# dam1941_extender.net
KiCad netlist of a schematic drawn in EAGLE
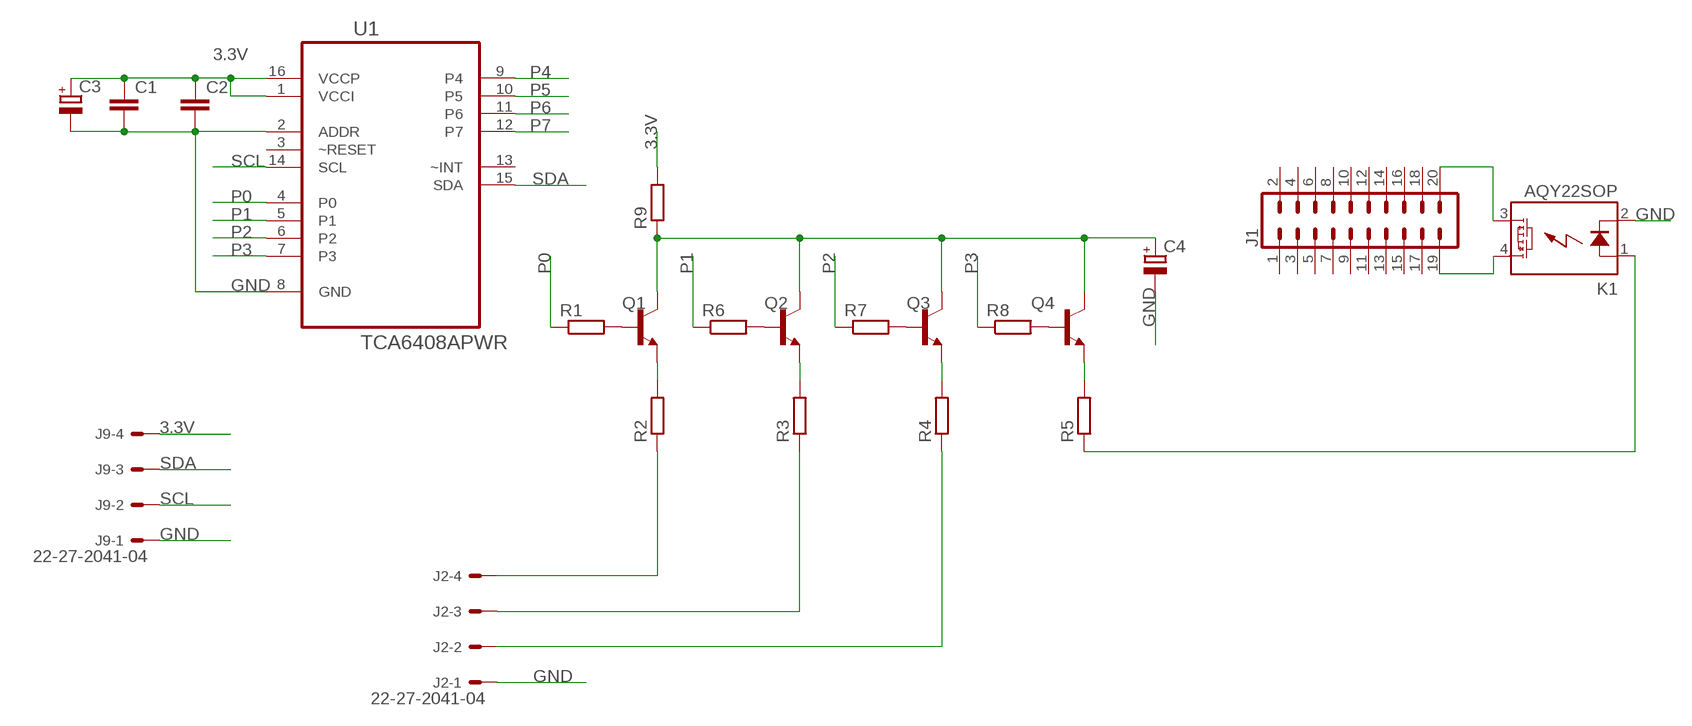
[diagram p0: schematic, sheet 1]

(export (version "E")
  (design (tool "Eeschema 10.0.6"))
  (components
    (comp (ref "C1")
      (value "C-EUC0805")
      (footprint "eagle-import:C0805")
      (libsource (lib "eagle-import") (part "C-EUC0805"))
    )
    (comp (ref "C2")
      (value "C-EUC0805")
      (footprint "eagle-import:C0805")
      (libsource (lib "eagle-import") (part "C-EUC0805"))
    )
    (comp (ref "C3")
      (value "CPOL-EUE2.5-6")
      (footprint "eagle-import:E2,5-6")
      (libsource (lib "eagle-import") (part "CPOL-EUE2.5-6"))
    )
    (comp (ref "C4")
      (value "CPOL-EUE2.5-6")
      (footprint "eagle-import:E2,5-6")
      (libsource (lib "eagle-import") (part "CPOL-EUE2.5-6"))
    )
    (comp (ref "J1")
      (value "CONN_10X22X10_LOCK")
      (footprint "eagle-import:2X10_LOCK")
      (libsource (lib "eagle-import") (part "CONN_10X22X10_LOCK"))
    )
    (comp (ref "J2")
      (value "22-27-2041-04")
      (footprint "eagle-import:6410-04")
      (fields (field (name "MF") "MOLEX"))
      (libsource (lib "eagle-import") (part "22-?-0427-2041"))
    )
    (comp (ref "J9")
      (value "22-27-2041-04")
      (footprint "eagle-import:6410-04")
      (fields (field (name "MF") "MOLEX"))
      (libsource (lib "eagle-import") (part "22-?-0427-2041"))
    )
    (comp (ref "K1")
      (value "AQY22SOP")
      (footprint "eagle-import:SOP04")
      (libsource (lib "eagle-import") (part "AQYSOP22"))
    )
    (comp (ref "Q1")
      (value "TRANSISTOR_BC850-NPN-SOT23-BEC")
      (footprint "eagle-import:TRANSISTOR_SOT23-BEC")
      (libsource (lib "eagle-import") (part "TRANSISTOR_-NPN-SOT23-BECBC850"))
    )
    (comp (ref "Q2")
      (value "TRANSISTOR_BC850-NPN-SOT23-BEC")
      (footprint "eagle-import:TRANSISTOR_SOT23-BEC")
      (libsource (lib "eagle-import") (part "TRANSISTOR_-NPN-SOT23-BECBC850"))
    )
    (comp (ref "Q3")
      (value "TRANSISTOR_BC850-NPN-SOT23-BEC")
      (footprint "eagle-import:TRANSISTOR_SOT23-BEC")
      (libsource (lib "eagle-import") (part "TRANSISTOR_-NPN-SOT23-BECBC850"))
    )
    (comp (ref "Q4")
      (value "TRANSISTOR_BC850-NPN-SOT23-BEC")
      (footprint "eagle-import:TRANSISTOR_SOT23-BEC")
      (libsource (lib "eagle-import") (part "TRANSISTOR_-NPN-SOT23-BECBC850"))
    )
    (comp (ref "R1")
      (value "R-EU_MELF0204W")
      (footprint "eagle-import:MINI_MELF-0204W")
      (libsource (lib "eagle-import") (part "R-EU_MELF0204W"))
    )
    (comp (ref "R2")
      (value "R-EU_MELF0204W")
      (footprint "eagle-import:MINI_MELF-0204W")
      (libsource (lib "eagle-import") (part "R-EU_MELF0204W"))
    )
    (comp (ref "R3")
      (value "R-EU_MELF0204W")
      (footprint "eagle-import:MINI_MELF-0204W")
      (libsource (lib "eagle-import") (part "R-EU_MELF0204W"))
    )
    (comp (ref "R4")
      (value "R-EU_MELF0204W")
      (footprint "eagle-import:MINI_MELF-0204W")
      (libsource (lib "eagle-import") (part "R-EU_MELF0204W"))
    )
    (comp (ref "R5")
      (value "R-EU_MELF0204W")
      (footprint "eagle-import:MINI_MELF-0204W")
      (libsource (lib "eagle-import") (part "R-EU_MELF0204W"))
    )
    (comp (ref "R6")
      (value "R-EU_MELF0204W")
      (footprint "eagle-import:MINI_MELF-0204W")
      (libsource (lib "eagle-import") (part "R-EU_MELF0204W"))
    )
    (comp (ref "R7")
      (value "R-EU_MELF0204W")
      (footprint "eagle-import:MINI_MELF-0204W")
      (libsource (lib "eagle-import") (part "R-EU_MELF0204W"))
    )
    (comp (ref "R8")
      (value "R-EU_MELF0204W")
      (footprint "eagle-import:MINI_MELF-0204W")
      (libsource (lib "eagle-import") (part "R-EU_MELF0204W"))
    )
    (comp (ref "R9")
      (value "R-EU_MELF0204W")
      (footprint "eagle-import:MINI_MELF-0204W")
      (libsource (lib "eagle-import") (part "R-EU_MELF0204W"))
    )
    (comp (ref "U1")
      (value "TCA6408APWR")
      (footprint "eagle-import:SOP65P640X120-16N")
      (libsource (lib "eagle-import") (part "TCA6408APWR"))
    )
  )
  (nets
    (net (code "1") (name "/3.3V") (class "Default")
      (node (ref "C1") (pin "1") (pinfunction "1_1") (pintype "passive"))
      (node (ref "C2") (pin "1") (pinfunction "1_1") (pintype "passive"))
      (node (ref "C3") (pin "+") (pinfunction "+_+") (pintype "passive"))
      (node (ref "J9") (pin "4") (pinfunction "S_4") (pintype "passive"))
      (node (ref "R9") (pin "2") (pinfunction "2_2") (pintype "passive"))
      (node (ref "U1") (pin "1") (pinfunction "VCCI_1") (pintype "power_in"))
      (node (ref "U1") (pin "16") (pinfunction "VCCP_16") (pintype "power_in"))
    )
    (net (code "2") (name "/GND") (class "Default")
      (node (ref "C1") (pin "2") (pinfunction "2_2") (pintype "passive"))
      (node (ref "C2") (pin "2") (pinfunction "2_2") (pintype "passive"))
      (node (ref "C3") (pin "-") (pinfunction "-_-") (pintype "passive"))
      (node (ref "C4") (pin "-") (pinfunction "-_-") (pintype "passive"))
      (node (ref "J2") (pin "1") (pinfunction "S_1") (pintype "passive"))
      (node (ref "J9") (pin "1") (pinfunction "S_1") (pintype "passive"))
      (node (ref "K1") (pin "2") (pinfunction "K_2") (pintype "passive"))
      (node (ref "U1") (pin "2") (pinfunction "ADDR_2") (pintype "input"))
      (node (ref "U1") (pin "8") (pinfunction "GND_8") (pintype "passive"))
    )
    (net (code "3") (name "/P0") (class "Default")
      (node (ref "R1") (pin "1") (pinfunction "1_1") (pintype "passive"))
      (node (ref "U1") (pin "4") (pinfunction "P0_4") (pintype "bidirectional"))
    )
    (net (code "4") (name "/P1") (class "Default")
      (node (ref "R6") (pin "1") (pinfunction "1_1") (pintype "passive"))
      (node (ref "U1") (pin "5") (pinfunction "P1_5") (pintype "bidirectional"))
    )
    (net (code "5") (name "/P2") (class "Default")
      (node (ref "R7") (pin "1") (pinfunction "1_1") (pintype "passive"))
      (node (ref "U1") (pin "6") (pinfunction "P2_6") (pintype "bidirectional"))
    )
    (net (code "6") (name "/P3") (class "Default")
      (node (ref "R8") (pin "1") (pinfunction "1_1") (pintype "passive"))
      (node (ref "U1") (pin "7") (pinfunction "P3_7") (pintype "bidirectional"))
    )
    (net (code "7") (name "/P4") (class "Default")
      (node (ref "U1") (pin "9") (pinfunction "P4_9") (pintype "bidirectional"))
    )
    (net (code "8") (name "/P5") (class "Default")
      (node (ref "U1") (pin "10") (pinfunction "P5_10") (pintype "bidirectional"))
    )
    (net (code "9") (name "/P6") (class "Default")
      (node (ref "U1") (pin "11") (pinfunction "P6_11") (pintype "bidirectional"))
    )
    (net (code "10") (name "/P7") (class "Default")
      (node (ref "U1") (pin "12") (pinfunction "P7_12") (pintype "bidirectional"))
    )
    (net (code "11") (name "/SCL") (class "Default")
      (node (ref "J9") (pin "2") (pinfunction "S_2") (pintype "passive"))
      (node (ref "U1") (pin "14") (pinfunction "SCL_14") (pintype "input"))
    )
    (net (code "12") (name "/SDA") (class "Default")
      (node (ref "J9") (pin "3") (pinfunction "S_3") (pintype "passive"))
      (node (ref "U1") (pin "15") (pinfunction "SDA_15") (pintype "bidirectional"))
    )
    (net (code "13") (name "Net-(C4-Pad+)") (class "Default")
      (node (ref "C4") (pin "+") (pinfunction "+_+") (pintype "passive"))
      (node (ref "Q1") (pin "C") (pinfunction "C_C") (pintype "passive"))
      (node (ref "Q2") (pin "C") (pinfunction "C_C") (pintype "passive"))
      (node (ref "Q3") (pin "C") (pinfunction "C_C") (pintype "passive"))
      (node (ref "Q4") (pin "C") (pinfunction "C_C") (pintype "passive"))
      (node (ref "R9") (pin "1") (pinfunction "1_1") (pintype "passive"))
    )
    (net (code "14") (name "Net-(J2B-S)") (class "Default")
      (node (ref "J2") (pin "2") (pinfunction "S_2") (pintype "passive"))
      (node (ref "R4") (pin "1") (pinfunction "1_1") (pintype "passive"))
    )
    (net (code "15") (name "Net-(J2C-S)") (class "Default")
      (node (ref "J2") (pin "3") (pinfunction "S_3") (pintype "passive"))
      (node (ref "R3") (pin "1") (pinfunction "1_1") (pintype "passive"))
    )
    (net (code "16") (name "Net-(J2D-S)") (class "Default")
      (node (ref "J2") (pin "4") (pinfunction "S_4") (pintype "passive"))
      (node (ref "R2") (pin "1") (pinfunction "1_1") (pintype "passive"))
    )
    (net (code "17") (name "Net-(K1-A)") (class "Default")
      (node (ref "K1") (pin "1") (pinfunction "A_1") (pintype "passive"))
      (node (ref "R5") (pin "1") (pinfunction "1_1") (pintype "passive"))
    )
    (net (code "18") (name "Net-(K1-DS1)") (class "Default")
      (node (ref "J1") (pin "19") (pinfunction "19_19") (pintype "passive"))
      (node (ref "K1") (pin "4") (pinfunction "DS1_4") (pintype "passive"))
    )
    (net (code "19") (name "Net-(K1-DS2)") (class "Default")
      (node (ref "J1") (pin "20") (pinfunction "20_20") (pintype "passive"))
      (node (ref "K1") (pin "3") (pinfunction "DS2_3") (pintype "passive"))
    )
    (net (code "20") (name "Net-(Q1-PadB)") (class "Default")
      (node (ref "Q1") (pin "B") (pinfunction "B_B") (pintype "passive"))
      (node (ref "R1") (pin "2") (pinfunction "2_2") (pintype "passive"))
    )
    (net (code "21") (name "Net-(Q1-PadE)") (class "Default")
      (node (ref "Q1") (pin "E") (pinfunction "E_E") (pintype "passive"))
      (node (ref "R2") (pin "2") (pinfunction "2_2") (pintype "passive"))
    )
    (net (code "22") (name "Net-(Q2-PadB)") (class "Default")
      (node (ref "Q2") (pin "B") (pinfunction "B_B") (pintype "passive"))
      (node (ref "R6") (pin "2") (pinfunction "2_2") (pintype "passive"))
    )
    (net (code "23") (name "Net-(Q2-PadE)") (class "Default")
      (node (ref "Q2") (pin "E") (pinfunction "E_E") (pintype "passive"))
      (node (ref "R3") (pin "2") (pinfunction "2_2") (pintype "passive"))
    )
    (net (code "24") (name "Net-(Q3-PadB)") (class "Default")
      (node (ref "Q3") (pin "B") (pinfunction "B_B") (pintype "passive"))
      (node (ref "R7") (pin "2") (pinfunction "2_2") (pintype "passive"))
    )
    (net (code "25") (name "Net-(Q3-PadE)") (class "Default")
      (node (ref "Q3") (pin "E") (pinfunction "E_E") (pintype "passive"))
      (node (ref "R4") (pin "2") (pinfunction "2_2") (pintype "passive"))
    )
    (net (code "26") (name "Net-(Q4-PadB)") (class "Default")
      (node (ref "Q4") (pin "B") (pinfunction "B_B") (pintype "passive"))
      (node (ref "R8") (pin "2") (pinfunction "2_2") (pintype "passive"))
    )
    (net (code "27") (name "Net-(Q4-PadE)") (class "Default")
      (node (ref "Q4") (pin "E") (pinfunction "E_E") (pintype "passive"))
      (node (ref "R5") (pin "2") (pinfunction "2_2") (pintype "passive"))
    )
    (net (code "28") (name "unconnected-(J1-Pad1)") (class "Default")
      (node (ref "J1") (pin "1") (pinfunction "1_1") (pintype "passive"))
    )
    (net (code "29") (name "unconnected-(J1-Pad2)") (class "Default")
      (node (ref "J1") (pin "2") (pinfunction "2_2") (pintype "passive"))
    )
    (net (code "30") (name "unconnected-(J1-Pad3)") (class "Default")
      (node (ref "J1") (pin "3") (pinfunction "3_3") (pintype "passive"))
    )
    (net (code "31") (name "unconnected-(J1-Pad4)") (class "Default")
      (node (ref "J1") (pin "4") (pinfunction "4_4") (pintype "passive"))
    )
    (net (code "32") (name "unconnected-(J1-Pad5)") (class "Default")
      (node (ref "J1") (pin "5") (pinfunction "5_5") (pintype "passive"))
    )
    (net (code "33") (name "unconnected-(J1-Pad6)") (class "Default")
      (node (ref "J1") (pin "6") (pinfunction "6_6") (pintype "passive"))
    )
    (net (code "34") (name "unconnected-(J1-Pad7)") (class "Default")
      (node (ref "J1") (pin "7") (pinfunction "7_7") (pintype "passive"))
    )
    (net (code "35") (name "unconnected-(J1-Pad8)") (class "Default")
      (node (ref "J1") (pin "8") (pinfunction "8_8") (pintype "passive"))
    )
    (net (code "36") (name "unconnected-(J1-Pad9)") (class "Default")
      (node (ref "J1") (pin "9") (pinfunction "9_9") (pintype "passive"))
    )
    (net (code "37") (name "unconnected-(J1-Pad10)") (class "Default")
      (node (ref "J1") (pin "10") (pinfunction "10_10") (pintype "passive"))
    )
    (net (code "38") (name "unconnected-(J1-Pad11)") (class "Default")
      (node (ref "J1") (pin "11") (pinfunction "11_11") (pintype "passive"))
    )
    (net (code "39") (name "unconnected-(J1-Pad12)") (class "Default")
      (node (ref "J1") (pin "12") (pinfunction "12_12") (pintype "passive"))
    )
    (net (code "40") (name "unconnected-(J1-Pad13)") (class "Default")
      (node (ref "J1") (pin "13") (pinfunction "13_13") (pintype "passive"))
    )
    (net (code "41") (name "unconnected-(J1-Pad14)") (class "Default")
      (node (ref "J1") (pin "14") (pinfunction "14_14") (pintype "passive"))
    )
    (net (code "42") (name "unconnected-(J1-Pad15)") (class "Default")
      (node (ref "J1") (pin "15") (pinfunction "15_15") (pintype "passive"))
    )
    (net (code "43") (name "unconnected-(J1-Pad16)") (class "Default")
      (node (ref "J1") (pin "16") (pinfunction "16_16") (pintype "passive"))
    )
    (net (code "44") (name "unconnected-(J1-Pad17)") (class "Default")
      (node (ref "J1") (pin "17") (pinfunction "17_17") (pintype "passive"))
    )
    (net (code "45") (name "unconnected-(J1-Pad18)") (class "Default")
      (node (ref "J1") (pin "18") (pinfunction "18_18") (pintype "passive"))
    )
    (net (code "46") (name "unconnected-(U1-~{INT}-Pad13)") (class "Default")
      (node (ref "U1") (pin "13") (pinfunction "~{INT}_13") (pintype "output"))
    )
    (net (code "47") (name "unconnected-(U1-~{RESET}-Pad3)") (class "Default")
      (node (ref "U1") (pin "3") (pinfunction "~{RESET}_3") (pintype "input"))
    )
  )
)
